# CCM0006.net
KiCad netlist of a schematic drawn in EAGLE
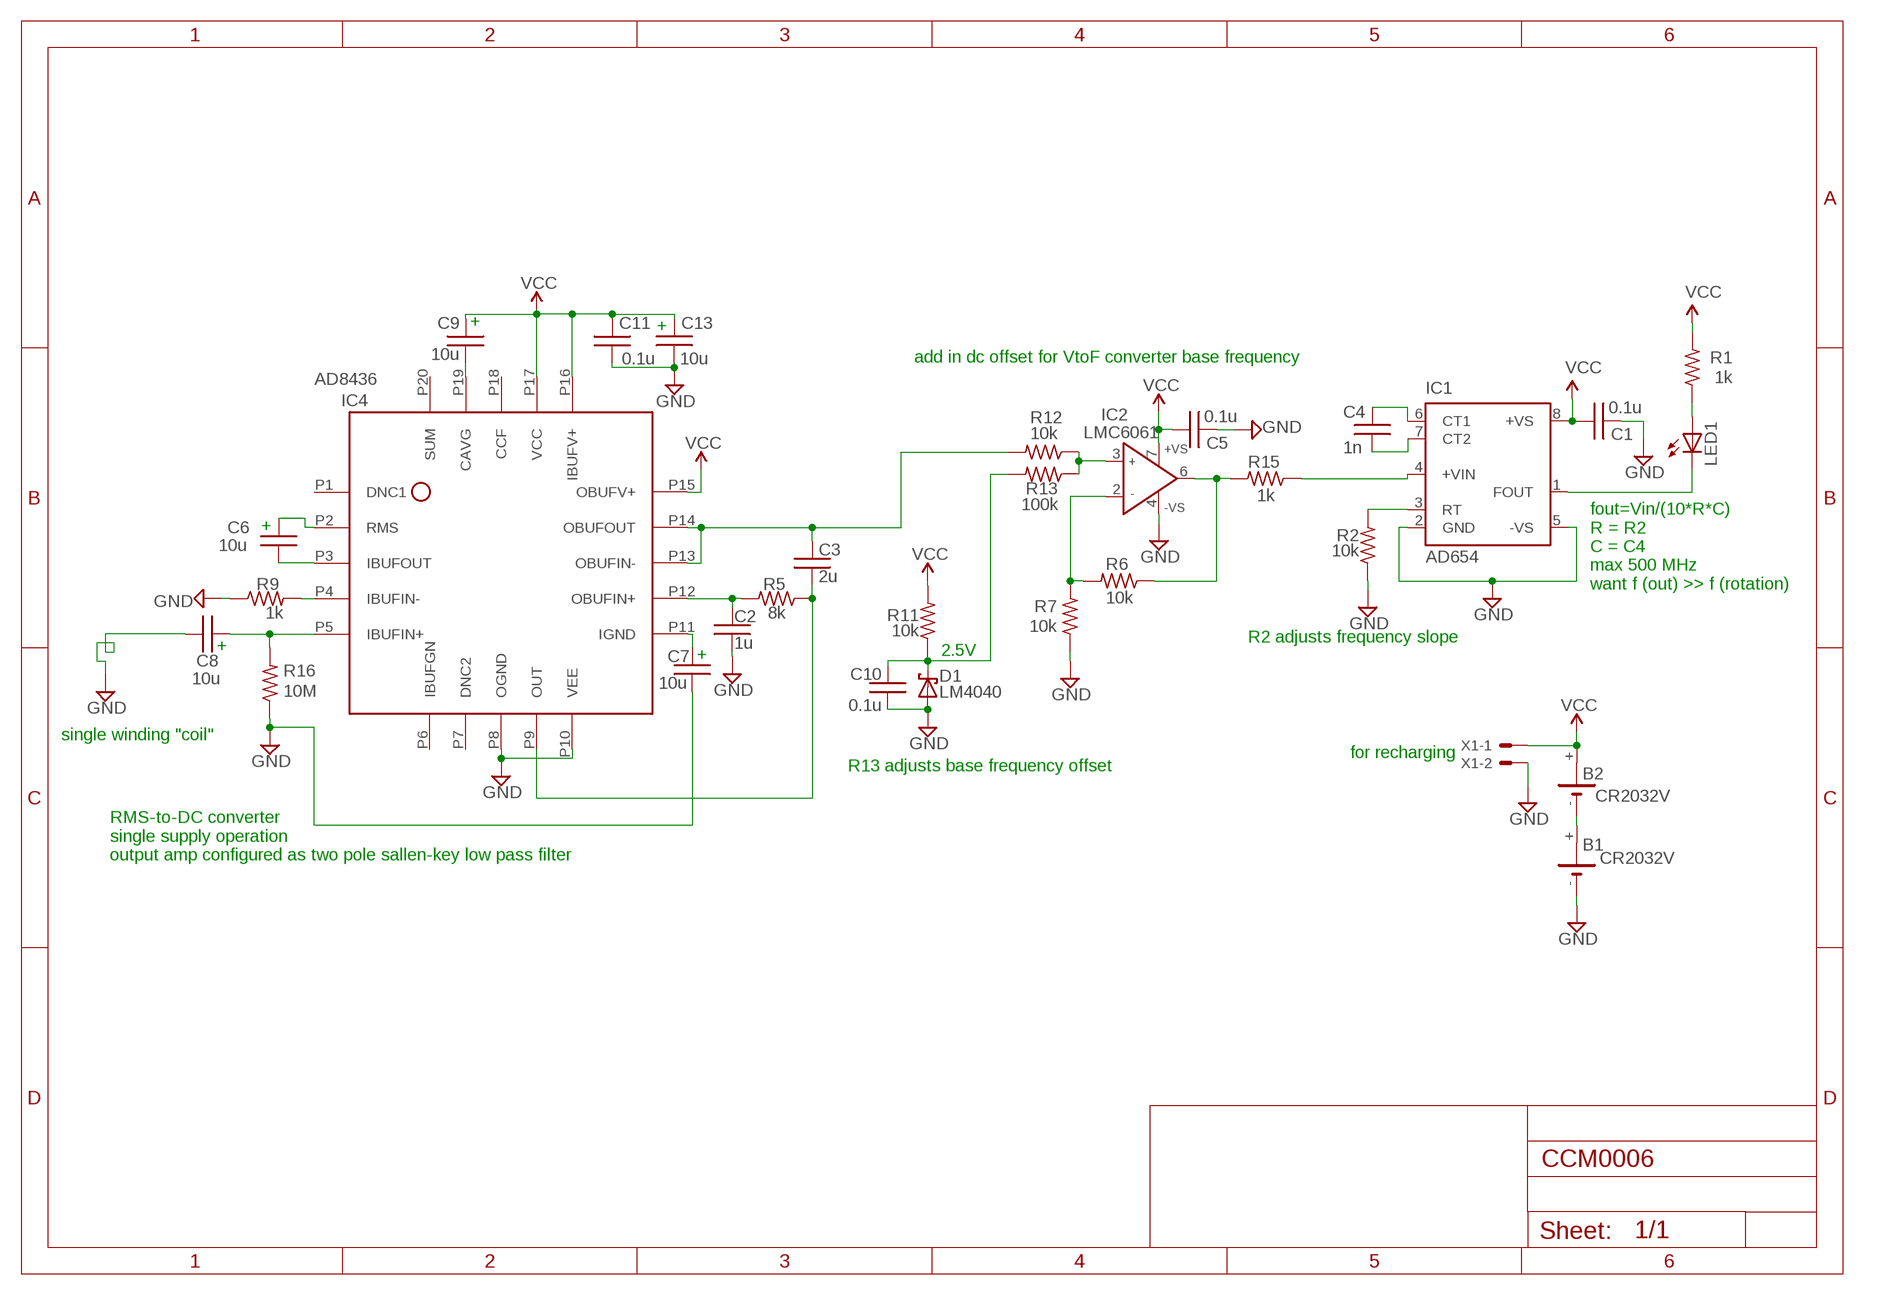
[diagram p0: schematic, sheet 1]

(export (version "E")
  (design (tool "Eeschema 10.0.6"))
  (components
    (comp (ref "B1")
      (value "CR2032V")
      (footprint "eagle-import:CR2032V")
      (libsource (lib "eagle-import") (part "CR2032V"))
    )
    (comp (ref "B2")
      (value "CR2032V")
      (footprint "eagle-import:CR2032V")
      (libsource (lib "eagle-import") (part "CR2032V"))
    )
    (comp (ref "C1")
      (value "0.1u")
      (footprint "eagle-import:0402")
      (libsource (lib "eagle-import") (part "CAPACITOR0402"))
    )
    (comp (ref "C2")
      (value "1u")
      (footprint "eagle-import:0402")
      (libsource (lib "eagle-import") (part "CAPACITOR0402"))
    )
    (comp (ref "C3")
      (value "2u")
      (footprint "eagle-import:0402")
      (libsource (lib "eagle-import") (part "CAPACITOR0402"))
    )
    (comp (ref "C4")
      (value "1n")
      (footprint "eagle-import:0402")
      (libsource (lib "eagle-import") (part "CAPACITOR0402"))
    )
    (comp (ref "C5")
      (value "0.1u")
      (footprint "eagle-import:0402")
      (libsource (lib "eagle-import") (part "CAPACITOR0402"))
    )
    (comp (ref "C6")
      (value "10u")
      (footprint "eagle-import:0805")
      (libsource (lib "eagle-import") (part "CAPACITOR0805"))
    )
    (comp (ref "C7")
      (value "10u")
      (footprint "eagle-import:0805")
      (libsource (lib "eagle-import") (part "CAPACITOR0805"))
    )
    (comp (ref "C8")
      (value "10u")
      (footprint "eagle-import:0805")
      (libsource (lib "eagle-import") (part "CAPACITOR0805"))
    )
    (comp (ref "C9")
      (value "10u")
      (footprint "eagle-import:0805")
      (libsource (lib "eagle-import") (part "CAPACITOR0805"))
    )
    (comp (ref "C10")
      (value "0.1u")
      (footprint "eagle-import:0402")
      (libsource (lib "eagle-import") (part "CAPACITOR0402"))
    )
    (comp (ref "C11")
      (value "0.1u")
      (footprint "eagle-import:0402")
      (libsource (lib "eagle-import") (part "CAPACITOR0402"))
    )
    (comp (ref "C13")
      (value "10u")
      (footprint "eagle-import:0805")
      (libsource (lib "eagle-import") (part "CAPACITOR0805"))
    )
    (comp (ref "D1")
      (value "LM4040")
      (footprint "eagle-import:SOT23")
      (libsource (lib "eagle-import") (part "LM4040"))
    )
    (comp (ref "IC1")
      (value "AD654")
      (footprint "eagle-import:SO08")
      (libsource (lib "eagle-import") (part "AD654"))
    )
    (comp (ref "IC2")
      (value "LMC6061")
      (footprint "eagle-import:SO8")
      (libsource (lib "eagle-import") (part "AD820R"))
    )
    (comp (ref "IC4")
      (value "AD8436")
      (footprint "eagle-import:CP-20-10")
      (libsource (lib "eagle-import") (part "AD8436"))
    )
    (comp (ref "LED1")
      (value "LED3MM")
      (footprint "eagle-import:LED3MM")
      (libsource (lib "eagle-import") (part "LED3MM"))
    )
    (comp (ref "R1")
      (value "1k")
      (footprint "eagle-import:0402")
      (libsource (lib "eagle-import") (part "RESISTOR0402"))
    )
    (comp (ref "R2")
      (value "10k")
      (footprint "eagle-import:0402")
      (libsource (lib "eagle-import") (part "RESISTOR0402"))
    )
    (comp (ref "R5")
      (value "8k")
      (footprint "eagle-import:0402")
      (libsource (lib "eagle-import") (part "RESISTOR0402"))
    )
    (comp (ref "R6")
      (value "10k")
      (footprint "eagle-import:0402")
      (libsource (lib "eagle-import") (part "RESISTOR0402"))
    )
    (comp (ref "R7")
      (value "10k")
      (footprint "eagle-import:0402")
      (libsource (lib "eagle-import") (part "RESISTOR0402"))
    )
    (comp (ref "R9")
      (value "1k")
      (footprint "eagle-import:0402")
      (libsource (lib "eagle-import") (part "RESISTOR0402"))
    )
    (comp (ref "R11")
      (value "10k")
      (footprint "eagle-import:0402")
      (libsource (lib "eagle-import") (part "RESISTOR0402"))
    )
    (comp (ref "R12")
      (value "10k")
      (footprint "eagle-import:0402")
      (libsource (lib "eagle-import") (part "RESISTOR0402"))
    )
    (comp (ref "R13")
      (value "100k")
      (footprint "eagle-import:0402")
      (libsource (lib "eagle-import") (part "RESISTOR0402"))
    )
    (comp (ref "R15")
      (value "1k")
      (footprint "eagle-import:0402")
      (libsource (lib "eagle-import") (part "RESISTOR0402"))
    )
    (comp (ref "R16")
      (value "10M")
      (footprint "eagle-import:0402")
      (libsource (lib "eagle-import") (part "RESISTOR0402"))
    )
    (comp (ref "X1")
      (value "22-23-2021")
      (footprint "eagle-import:22-23-2021")
      (fields (field (name "MF") "MOLEX"))
      (libsource (lib "eagle-import") (part "22-23-2021"))
    )
  )
  (nets
    (net (code "1") (name "GND") (class "Default")
      (node (ref "B1") (pin "-") (pinfunction "-_-") (pintype "passive"))
      (node (ref "C1") (pin "2") (pinfunction "2_2") (pintype "passive"))
      (node (ref "C10") (pin "2") (pinfunction "2_2") (pintype "passive"))
      (node (ref "C11") (pin "2") (pinfunction "2_2") (pintype "passive"))
      (node (ref "C13") (pin "1") (pinfunction "1_1") (pintype "passive"))
      (node (ref "C2") (pin "1") (pinfunction "1_1") (pintype "passive"))
      (node (ref "C5") (pin "2") (pinfunction "2_2") (pintype "passive"))
      (node (ref "C7") (pin "1") (pinfunction "1_1") (pintype "passive"))
      (node (ref "C8") (pin "1") (pinfunction "1_1") (pintype "passive"))
      (node (ref "D1") (pin "2") (pinfunction "A_2") (pintype "passive"))
      (node (ref "IC1") (pin "2") (pinfunction "GND_2") (pintype "power_in"))
      (node (ref "IC1") (pin "5") (pinfunction "-VS_5") (pintype "power_in"))
      (node (ref "IC2") (pin "4") (pinfunction "-VS_4") (pintype "input"))
      (node (ref "IC4") (pin "P10") (pinfunction "VEE_P10") (pintype "bidirectional"))
      (node (ref "IC4") (pin "P8") (pinfunction "OGND_P8") (pintype "bidirectional"))
      (node (ref "R16") (pin "1") (pinfunction "1_1") (pintype "passive"))
      (node (ref "R2") (pin "1") (pinfunction "1_1") (pintype "passive"))
      (node (ref "R7") (pin "1") (pinfunction "1_1") (pintype "passive"))
      (node (ref "R9") (pin "1") (pinfunction "1_1") (pintype "passive"))
      (node (ref "X1") (pin "2") (pinfunction "S_2") (pintype "passive"))
    )
    (net (code "2") (name "Net-(B1-Pad+)") (class "Default")
      (node (ref "B1") (pin "+") (pinfunction "+_+") (pintype "passive"))
      (node (ref "B2") (pin "-") (pinfunction "-_-") (pintype "passive"))
    )
    (net (code "3") (name "Net-(D1-C)") (class "Default")
      (node (ref "C10") (pin "1") (pinfunction "1_1") (pintype "passive"))
      (node (ref "D1") (pin "1") (pinfunction "C_1") (pintype "passive"))
      (node (ref "R11") (pin "1") (pinfunction "1_1") (pintype "passive"))
      (node (ref "R13") (pin "2") (pinfunction "2_2") (pintype "passive"))
    )
    (net (code "4") (name "Net-(IC1-+VIN)") (class "Default")
      (node (ref "IC1") (pin "4") (pinfunction "+VIN_4") (pintype "input"))
      (node (ref "R15") (pin "1") (pinfunction "1_1") (pintype "passive"))
    )
    (net (code "5") (name "Net-(IC1-CT1)") (class "Default")
      (node (ref "C4") (pin "2") (pinfunction "2_2") (pintype "passive"))
      (node (ref "IC1") (pin "6") (pinfunction "CT1_6") (pintype "passive"))
    )
    (net (code "6") (name "Net-(IC1-CT2)") (class "Default")
      (node (ref "C4") (pin "1") (pinfunction "1_1") (pintype "passive"))
      (node (ref "IC1") (pin "7") (pinfunction "CT2_7") (pintype "passive"))
    )
    (net (code "7") (name "Net-(IC1-FOUT)") (class "Default")
      (node (ref "IC1") (pin "1") (pinfunction "FOUT_1") (pintype "open_collector"))
      (node (ref "LED1") (pin "K") (pinfunction "C_K") (pintype "passive"))
    )
    (net (code "8") (name "Net-(IC1-RT)") (class "Default")
      (node (ref "IC1") (pin "3") (pinfunction "RT_3") (pintype "passive"))
      (node (ref "R2") (pin "2") (pinfunction "2_2") (pintype "passive"))
    )
    (net (code "9") (name "Net-(IC2-IN+)") (class "Default")
      (node (ref "IC2") (pin "3") (pinfunction "IN+_3") (pintype "input"))
      (node (ref "R12") (pin "1") (pinfunction "1_1") (pintype "passive"))
      (node (ref "R13") (pin "1") (pinfunction "1_1") (pintype "passive"))
    )
    (net (code "10") (name "Net-(IC2-IN-)") (class "Default")
      (node (ref "IC2") (pin "2") (pinfunction "IN-_2") (pintype "input"))
      (node (ref "R6") (pin "2") (pinfunction "2_2") (pintype "passive"))
      (node (ref "R7") (pin "2") (pinfunction "2_2") (pintype "passive"))
    )
    (net (code "11") (name "Net-(IC2-OUT)") (class "Default")
      (node (ref "IC2") (pin "6") (pinfunction "OUT_6") (pintype "output"))
      (node (ref "R15") (pin "2") (pinfunction "2_2") (pintype "passive"))
      (node (ref "R6") (pin "1") (pinfunction "1_1") (pintype "passive"))
    )
    (net (code "12") (name "Net-(IC4-CAVG)") (class "Default")
      (node (ref "C9") (pin "2") (pinfunction "2_2") (pintype "passive"))
      (node (ref "IC4") (pin "P19") (pinfunction "CAVG_P19") (pintype "bidirectional"))
    )
    (net (code "13") (name "Net-(IC4-IBUFIN+)") (class "Default")
      (node (ref "C8") (pin "2") (pinfunction "2_2") (pintype "passive"))
      (node (ref "IC4") (pin "P5") (pinfunction "IBUFIN+_P5") (pintype "bidirectional"))
      (node (ref "R16") (pin "2") (pinfunction "2_2") (pintype "passive"))
    )
    (net (code "14") (name "Net-(IC4-IBUFIN-)") (class "Default")
      (node (ref "IC4") (pin "P4") (pinfunction "IBUFIN-_P4") (pintype "bidirectional"))
      (node (ref "R9") (pin "2") (pinfunction "2_2") (pintype "passive"))
    )
    (net (code "15") (name "Net-(IC4-IBUFOUT)") (class "Default")
      (node (ref "C6") (pin "1") (pinfunction "1_1") (pintype "passive"))
      (node (ref "IC4") (pin "P3") (pinfunction "IBUFOUT_P3") (pintype "bidirectional"))
    )
    (net (code "16") (name "Net-(IC4-IGND)") (class "Default")
      (node (ref "C7") (pin "2") (pinfunction "2_2") (pintype "passive"))
      (node (ref "IC4") (pin "P11") (pinfunction "IGND_P11") (pintype "bidirectional"))
    )
    (net (code "17") (name "Net-(IC4-OBUFIN+)") (class "Default")
      (node (ref "C2") (pin "2") (pinfunction "2_2") (pintype "passive"))
      (node (ref "IC4") (pin "P12") (pinfunction "OBUFIN+_P12") (pintype "bidirectional"))
      (node (ref "R5") (pin "2") (pinfunction "2_2") (pintype "passive"))
    )
    (net (code "18") (name "Net-(IC4-OBUFIN-)") (class "Default")
      (node (ref "C3") (pin "1") (pinfunction "1_1") (pintype "passive"))
      (node (ref "IC4") (pin "P13") (pinfunction "OBUFIN-_P13") (pintype "bidirectional"))
      (node (ref "IC4") (pin "P14") (pinfunction "OBUFOUT_P14") (pintype "bidirectional"))
      (node (ref "R12") (pin "2") (pinfunction "2_2") (pintype "passive"))
    )
    (net (code "19") (name "Net-(IC4-OUT)") (class "Default")
      (node (ref "C3") (pin "2") (pinfunction "2_2") (pintype "passive"))
      (node (ref "IC4") (pin "P9") (pinfunction "OUT_P9") (pintype "bidirectional"))
      (node (ref "R5") (pin "1") (pinfunction "1_1") (pintype "passive"))
    )
    (net (code "20") (name "Net-(IC4-RMS)") (class "Default")
      (node (ref "C6") (pin "2") (pinfunction "2_2") (pintype "passive"))
      (node (ref "IC4") (pin "P2") (pinfunction "RMS_P2") (pintype "bidirectional"))
    )
    (net (code "21") (name "Net-(LED1-PadA)") (class "Default")
      (node (ref "LED1") (pin "A") (pinfunction "A_A") (pintype "passive"))
      (node (ref "R1") (pin "1") (pinfunction "1_1") (pintype "passive"))
    )
    (net (code "22") (name "VCC") (class "Default")
      (node (ref "B2") (pin "+") (pinfunction "+_+") (pintype "passive"))
      (node (ref "C1") (pin "1") (pinfunction "1_1") (pintype "passive"))
      (node (ref "C11") (pin "1") (pinfunction "1_1") (pintype "passive"))
      (node (ref "C13") (pin "2") (pinfunction "2_2") (pintype "passive"))
      (node (ref "C5") (pin "1") (pinfunction "1_1") (pintype "passive"))
      (node (ref "C9") (pin "1") (pinfunction "1_1") (pintype "passive"))
      (node (ref "IC1") (pin "8") (pinfunction "+VS_8") (pintype "power_in"))
      (node (ref "IC2") (pin "7") (pinfunction "+VS_7") (pintype "input"))
      (node (ref "IC4") (pin "P15") (pinfunction "OBUFV+_P15") (pintype "bidirectional"))
      (node (ref "IC4") (pin "P16") (pinfunction "IBUFV+_P16") (pintype "bidirectional"))
      (node (ref "IC4") (pin "P17") (pinfunction "VCC_P17") (pintype "bidirectional"))
      (node (ref "R1") (pin "2") (pinfunction "2_2") (pintype "passive"))
      (node (ref "R11") (pin "2") (pinfunction "2_2") (pintype "passive"))
      (node (ref "X1") (pin "1") (pinfunction "S_1") (pintype "passive"))
    )
    (net (code "23") (name "unconnected-(B1-+-Pad+@1)") (class "Default")
      (node (ref "B1") (pin "+@1") (pinfunction "+_+@1") (pintype "passive"))
    )
    (net (code "24") (name "unconnected-(B2-+-Pad+@1)") (class "Default")
      (node (ref "B2") (pin "+@1") (pinfunction "+_+@1") (pintype "passive"))
    )
    (net (code "25") (name "unconnected-(IC4-CCF-PadP18)") (class "Default")
      (node (ref "IC4") (pin "P18") (pinfunction "CCF_P18") (pintype "bidirectional"))
    )
    (net (code "26") (name "unconnected-(IC4-DNC1-PadP1)") (class "Default")
      (node (ref "IC4") (pin "P1") (pinfunction "DNC1_P1") (pintype "no_connect"))
    )
    (net (code "27") (name "unconnected-(IC4-DNC2-PadP7)") (class "Default")
      (node (ref "IC4") (pin "P7") (pinfunction "DNC2_P7") (pintype "bidirectional"))
    )
    (net (code "28") (name "unconnected-(IC4-IBUFGN-PadP6)") (class "Default")
      (node (ref "IC4") (pin "P6") (pinfunction "IBUFGN_P6") (pintype "bidirectional"))
    )
    (net (code "29") (name "unconnected-(IC4-SUM-PadP20)") (class "Default")
      (node (ref "IC4") (pin "P20") (pinfunction "SUM_P20") (pintype "bidirectional"))
    )
  )
)
